# PainRegister_MCU.net
KiCad netlist of a schematic drawn in Altium Designer
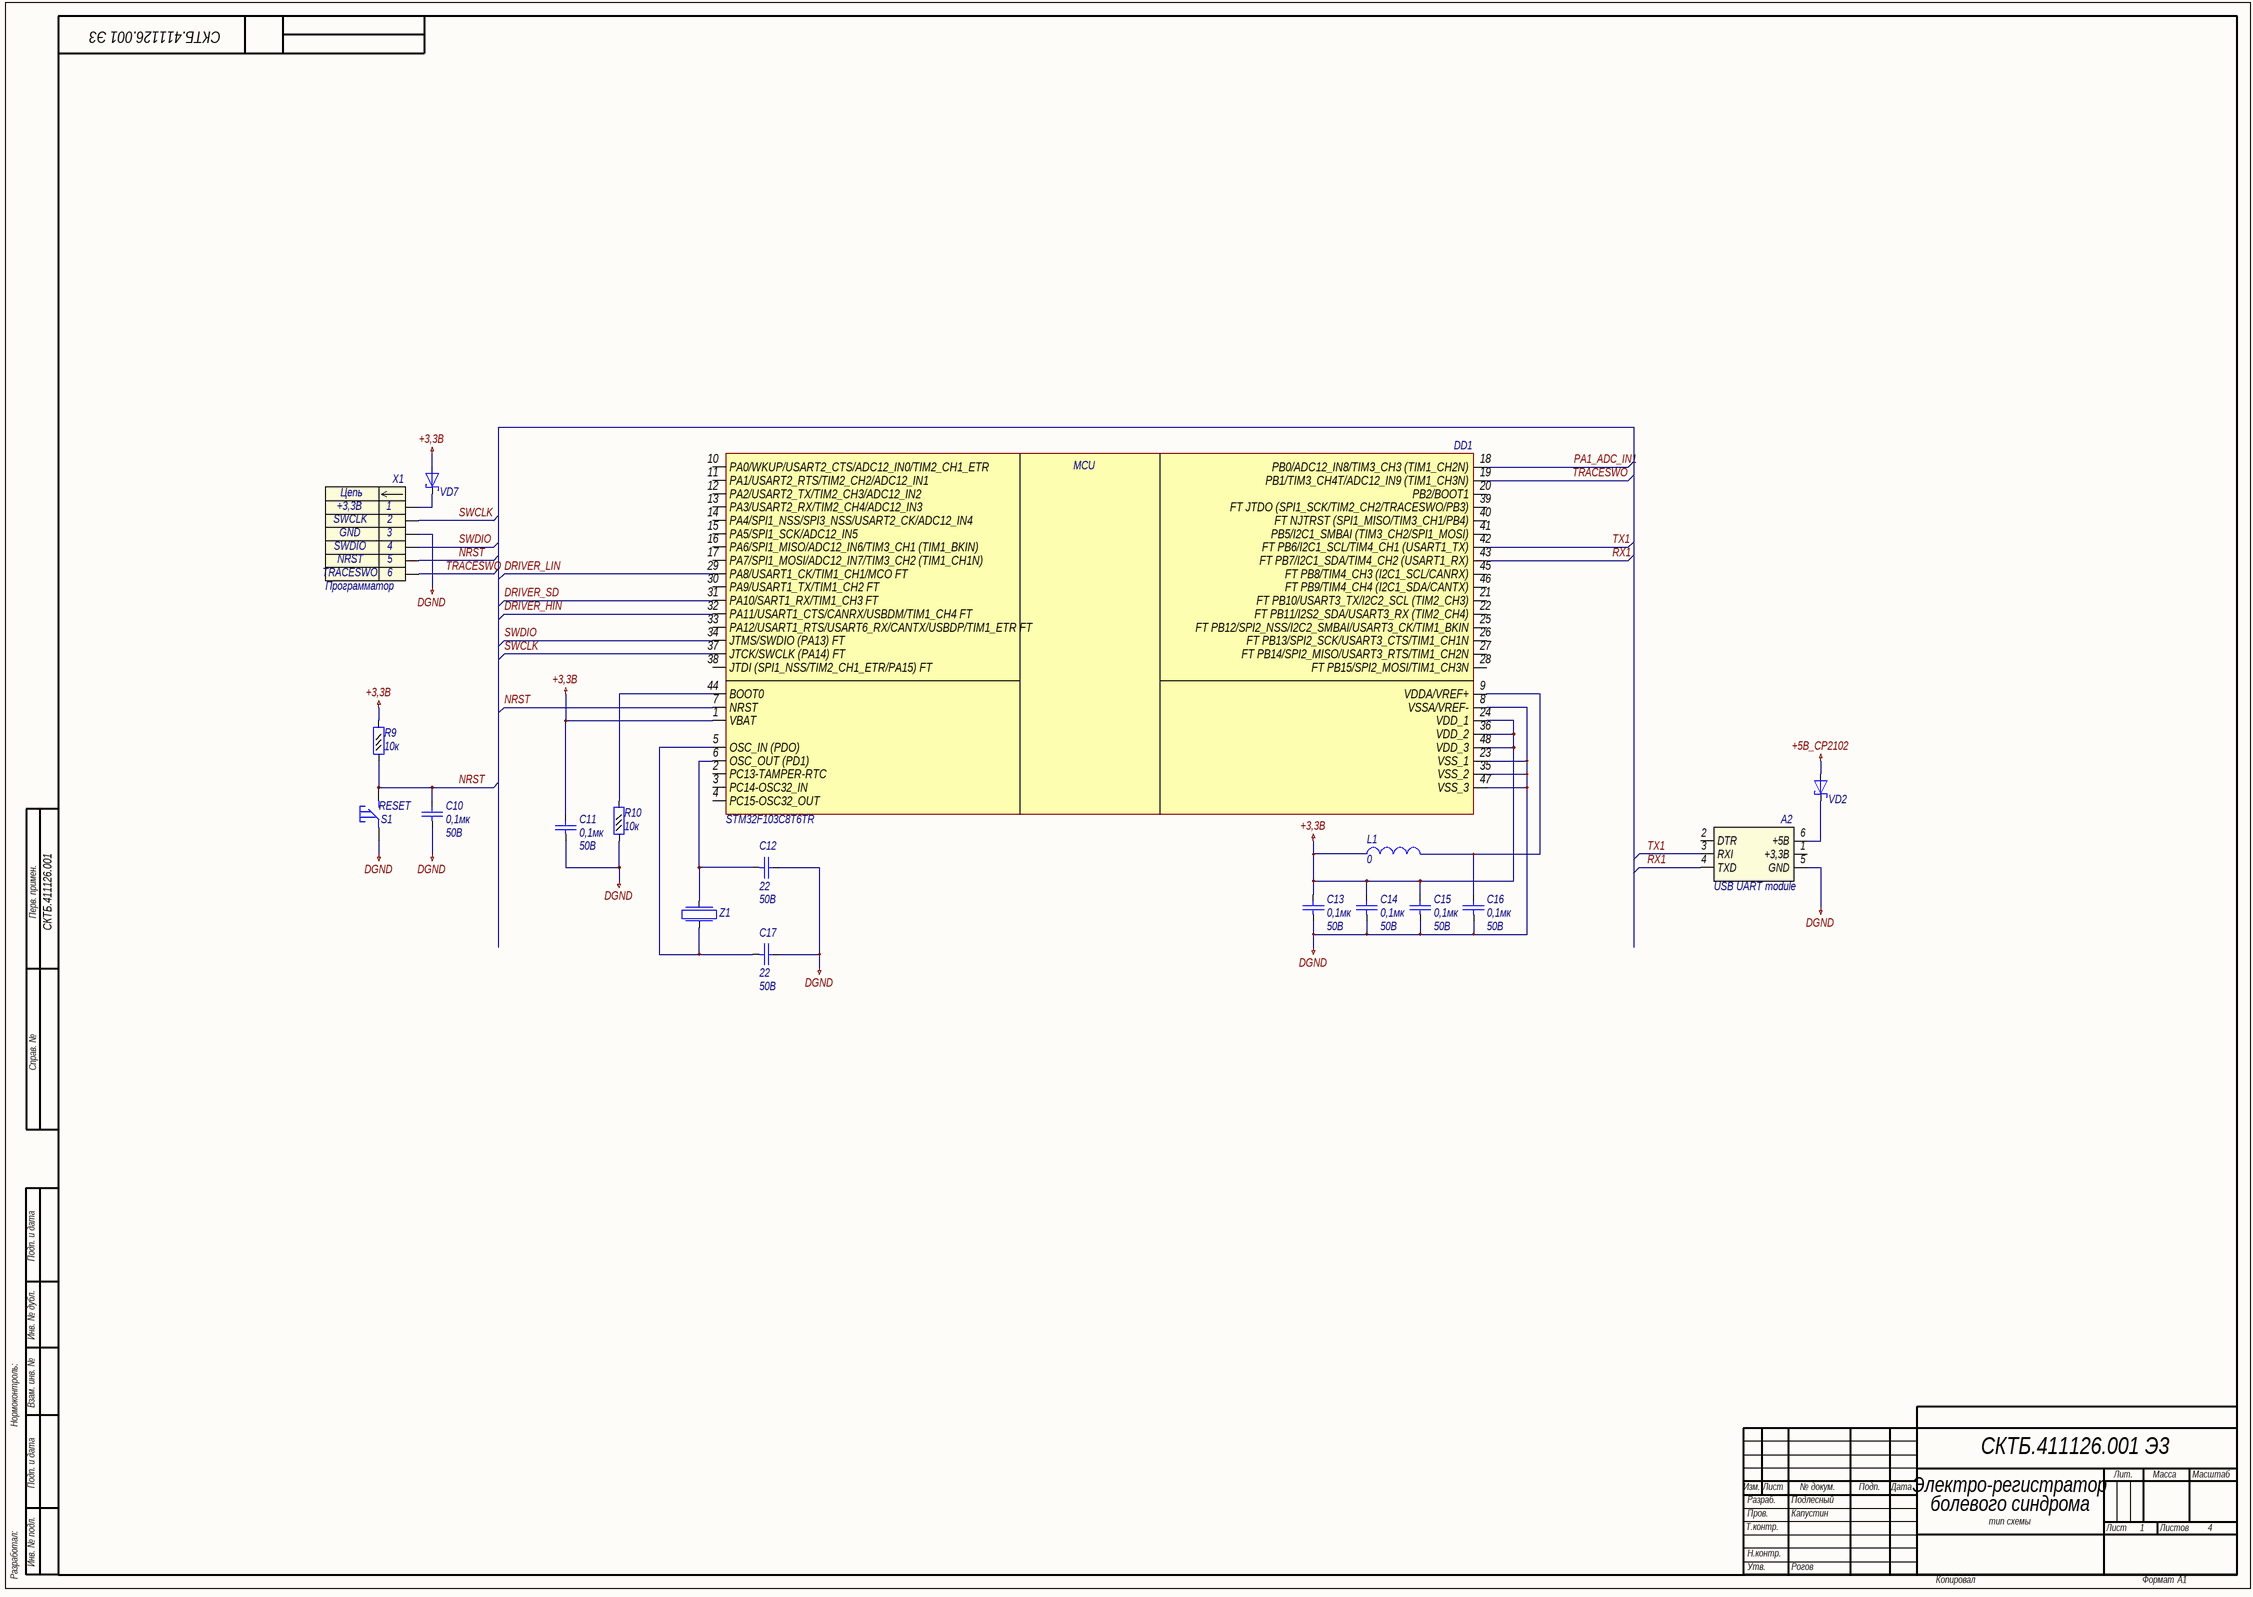
[diagram p0: PainRegister_MCU.SchDoc]

(export (version "E")
  (design (tool "Eeschema 10.0.6"))
  (components
    (comp (ref "A2")
      (value "USB UART module")
      (footprint "USB UART CP2102")
      (libsource (lib "MOP44") (part "USB UART"))
    )
    (comp (ref "C10")
      (value "0,1мк")
      (footprint "C0603")
      (description "Конденсатор")
      (fields
        (field (name "VOLTAGE") "50B")
        (field (name "PART NUMBER") "GRM188R71H104KA93D")
        (field (name "Comment") "Capacitor")
      )
      (libsource (lib "MOP44") (part "Capacitor"))
    )
    (comp (ref "C11")
      (value "0,1мк")
      (footprint "C0603")
      (description "Конденсатор")
      (fields
        (field (name "VOLTAGE") "50B")
        (field (name "PART NUMBER") "GRM188R71H104KA93D")
        (field (name "Comment") "Capacitor")
      )
      (libsource (lib "MOP44") (part "Capacitor"))
    )
    (comp (ref "C12")
      (value "22")
      (footprint "C0603")
      (description "Конденсатор")
      (fields
        (field (name "VOLTAGE") "50B")
        (field (name "PART NUMBER") "CC0603JRNPO9BN220")
        (field (name "Comment") "Capacitor")
      )
      (libsource (lib "MOP44") (part "Capacitor"))
    )
    (comp (ref "C13")
      (value "0,1мк")
      (footprint "C0603")
      (description "Конденсатор")
      (fields
        (field (name "VOLTAGE") "50B")
        (field (name "PART NUMBER") "GRM188R71H104KA93D")
        (field (name "Comment") "Capacitor")
      )
      (libsource (lib "MOP44") (part "Capacitor"))
    )
    (comp (ref "C14")
      (value "0,1мк")
      (footprint "C0603")
      (description "Конденсатор")
      (fields
        (field (name "VOLTAGE") "50B")
        (field (name "PART NUMBER") "GRM188R71H104KA93D")
        (field (name "Comment") "Capacitor")
      )
      (libsource (lib "MOP44") (part "Capacitor"))
    )
    (comp (ref "C15")
      (value "0,1мк")
      (footprint "C0603")
      (description "Конденсатор")
      (fields
        (field (name "VOLTAGE") "50B")
        (field (name "PART NUMBER") "GRM188R71H104KA93D")
        (field (name "Comment") "Capacitor")
      )
      (libsource (lib "MOP44") (part "Capacitor"))
    )
    (comp (ref "C16")
      (value "0,1мк")
      (footprint "C0603")
      (description "Конденсатор")
      (fields
        (field (name "VOLTAGE") "50B")
        (field (name "PART NUMBER") "GRM188R71H104KA93D")
        (field (name "Comment") "Capacitor")
      )
      (libsource (lib "MOP44") (part "Capacitor"))
    )
    (comp (ref "C17")
      (value "22")
      (footprint "C0603")
      (description "Конденсатор")
      (fields
        (field (name "VOLTAGE") "50B")
        (field (name "PART NUMBER") "CC0603JRNPO9BN220")
        (field (name "Comment") "Capacitor")
      )
      (libsource (lib "MOP44") (part "Capacitor"))
    )
    (comp (ref "DD1")
      (value "STM32F103C8T6TR")
      (footprint "LQFP48")
      (fields (field (name "PART NUMBER") "STM32F103C8T6TR"))
      (libsource (lib "MOP44") (part "STM32F103C8T6TR"))
    )
    (comp (ref "L1")
      (value "0")
      (footprint "L0603")
      (description "EMI Suppression Filter")
      (fields (field (name "PART NUMBER") "BLM18PG181SN1D") (field (name "Comment") "Inductor"))
      (libsource (lib "MOP44") (part "Inductor"))
    )
    (comp (ref "R9")
      (value "10к")
      (footprint "R0603")
      (description "Резистор")
      (fields (field (name "PART NUMBER") "RC0603FR-0710KL") (field (name "POWER") "0,062Вт"))
      (libsource (lib "MOP44") (part "Resistor_0,062Вт"))
    )
    (comp (ref "R10")
      (value "10к")
      (footprint "R0603")
      (description "Резистор")
      (fields (field (name "PART NUMBER") "RC0603FR-0710KL") (field (name "POWER") "0,062Вт"))
      (libsource (lib "MOP44") (part "Resistor_0,062Вт"))
    )
    (comp (ref "S1")
      (value "RESET")
      (footprint "Button_SMD")
      (description "Кнопка")
      (libsource (lib "MOP44") (part "Button"))
    )
    (comp (ref "VD2")
      (value "DiodeSchottky")
      (footprint "SOD-523")
      (description "Диод Шоттки")
      (fields (field (name "PART NUMBER") "PMEG2010AEB.115"))
      (libsource (lib "MOP44") (part "DiodeSchottky"))
    )
    (comp (ref "VD7")
      (value "DiodeSchottky")
      (footprint "SOD-523")
      (description "Диод Шоттки")
      (fields (field (name "PART NUMBER") "PMEG2010AEB.115"))
      (libsource (lib "MOP44") (part "DiodeSchottky"))
    )
    (comp (ref "X1")
      (value "Программатор")
      (footprint "PLS-6")
      (description "Разъем - 6 конт. вилка")
      (fields (field (name "PART NUMBER") "DS1021-1*6SF112-B"))
      (libsource (lib "MOP44") (part "Header_6_plg"))
    )
    (comp (ref "Z1")
      (value "Crystal")
      (footprint "QSMD5.0x3.2x1.0")
      (description "Кварцевый резонатор")
      (fields (field (name "PART NUMBER") "KX-9A"))
      (libsource (lib "MOP44") (part "Crystal"))
    )
  )
  (nets
    (net (code "1") (name "+3,3В") (class "Default")
      (node (ref "C11") (pin "2") (pinfunction "2_2") (pintype "passive"))
      (node (ref "C13") (pin "2") (pinfunction "2_2") (pintype "passive"))
      (node (ref "C14") (pin "2") (pinfunction "2_2") (pintype "passive"))
      (node (ref "C15") (pin "2") (pinfunction "2_2") (pintype "passive"))
      (node (ref "DD1") (pin "1") (pinfunction "VBAT_1") (pintype "passive"))
      (node (ref "DD1") (pin "24") (pinfunction "VDD_1_24") (pintype "passive"))
      (node (ref "DD1") (pin "36") (pinfunction "VDD_2_36") (pintype "passive"))
      (node (ref "DD1") (pin "48") (pinfunction "VDD_3_48") (pintype "passive"))
      (node (ref "L1") (pin "1") (pinfunction "1_1") (pintype "passive"))
      (node (ref "R9") (pin "2") (pinfunction "2_2") (pintype "passive"))
      (node (ref "VD7") (pin "2") (pinfunction "A_2") (pintype "passive"))
    )
    (net (code "2") (name "+5B_CP2102") (class "Default")
      (node (ref "VD2") (pin "2") (pinfunction "A_2") (pintype "passive"))
    )
    (net (code "3") (name "/DRIVER_HIN") (class "Default")
      (node (ref "DD1") (pin "32") (pinfunction "PA11/USART1_CTS/CANRX/USBDM/TIM1_CH4_FT_32") (pintype "passive"))
    )
    (net (code "4") (name "/DRIVER_LIN") (class "Default")
      (node (ref "DD1") (pin "29") (pinfunction "PA8/USART1_CK/TIM1_CH1/MCO_FT_29") (pintype "passive"))
    )
    (net (code "5") (name "/DRIVER_SD") (class "Default")
      (node (ref "DD1") (pin "31") (pinfunction "PA10/SART1_RX/TIM1_CH3_FT_31") (pintype "passive"))
    )
    (net (code "6") (name "/NRST") (class "Default")
      (node (ref "C10") (pin "2") (pinfunction "2_2") (pintype "passive"))
      (node (ref "DD1") (pin "7") (pinfunction "NRST_7") (pintype "passive"))
      (node (ref "R9") (pin "1") (pinfunction "1_1") (pintype "passive"))
      (node (ref "S1") (pin "4") (pinfunction "4_4") (pintype "passive"))
      (node (ref "X1") (pin "5") (pinfunction "5_5") (pintype "passive"))
    )
    (net (code "7") (name "/PA1_ADC_IN1") (class "Default")
      (node (ref "DD1") (pin "18") (pinfunction "PB0/ADC12_IN8/TIM3_CH3_(TIM1_CH2N)_18") (pintype "passive"))
    )
    (net (code "8") (name "/RX1") (class "Default")
      (node (ref "A2") (pin "4") (pinfunction "TXD_4") (pintype "power_in"))
      (node (ref "DD1") (pin "43") (pinfunction "FT_PB7/I2C1_SDA/TIM4_CH2_(USART1_RX)_43") (pintype "passive"))
    )
    (net (code "9") (name "/SWCLK") (class "Default")
      (node (ref "DD1") (pin "37") (pinfunction "JTCK/SWCLK_(PA14)_FT_37") (pintype "passive"))
      (node (ref "X1") (pin "2") (pinfunction "2_2") (pintype "passive"))
    )
    (net (code "10") (name "/SWDIO") (class "Default")
      (node (ref "DD1") (pin "34") (pinfunction "JTMS/SWDIO_(PA13)_FT_34") (pintype "passive"))
      (node (ref "X1") (pin "4") (pinfunction "4_4") (pintype "passive"))
    )
    (net (code "11") (name "/TRACESWO") (class "Default")
      (node (ref "DD1") (pin "19") (pinfunction "PB1/TIM3_CH4T/ADC12_IN9_(TIM1_CH3N)_19") (pintype "passive"))
      (node (ref "X1") (pin "6") (pinfunction "6_6") (pintype "passive"))
    )
    (net (code "12") (name "/TX1") (class "Default")
      (node (ref "A2") (pin "3") (pinfunction "RXI_3") (pintype "power_in"))
      (node (ref "DD1") (pin "42") (pinfunction "FT_PB6/I2C1_SCL/TIM4_CH1_(USART1_TX)_42") (pintype "passive"))
    )
    (net (code "13") (name "DGND") (class "Default")
      (node (ref "A2") (pin "5") (pinfunction "GND_5") (pintype "power_in"))
      (node (ref "C10") (pin "1") (pinfunction "1_1") (pintype "passive"))
      (node (ref "C11") (pin "1") (pinfunction "1_1") (pintype "passive"))
      (node (ref "C12") (pin "2") (pinfunction "2_2") (pintype "passive"))
      (node (ref "C13") (pin "1") (pinfunction "1_1") (pintype "passive"))
      (node (ref "C14") (pin "1") (pinfunction "1_1") (pintype "passive"))
      (node (ref "C15") (pin "1") (pinfunction "1_1") (pintype "passive"))
      (node (ref "C16") (pin "1") (pinfunction "1_1") (pintype "passive"))
      (node (ref "C17") (pin "2") (pinfunction "2_2") (pintype "passive"))
      (node (ref "DD1") (pin "23") (pinfunction "VSS_1_23") (pintype "passive"))
      (node (ref "DD1") (pin "35") (pinfunction "VSS_2_35") (pintype "passive"))
      (node (ref "DD1") (pin "47") (pinfunction "VSS_3_47") (pintype "passive"))
      (node (ref "DD1") (pin "8") (pinfunction "VSSA/VREF-_8") (pintype "passive"))
      (node (ref "R10") (pin "1") (pinfunction "1_1") (pintype "passive"))
      (node (ref "S1") (pin "1") (pinfunction "1_1") (pintype "passive"))
      (node (ref "X1") (pin "3") (pinfunction "3_3") (pintype "passive"))
    )
    (net (code "14") (name "Net-(A2-+5B)") (class "Default")
      (node (ref "A2") (pin "6") (pinfunction "+5B_6") (pintype "power_in"))
      (node (ref "VD2") (pin "1") (pinfunction "K_1") (pintype "passive"))
    )
    (net (code "15") (name "Net-(DD1-BOOT0)") (class "Default")
      (node (ref "DD1") (pin "44") (pinfunction "BOOT0_44") (pintype "passive"))
      (node (ref "R10") (pin "2") (pinfunction "2_2") (pintype "passive"))
    )
    (net (code "16") (name "Net-(DD1-OSC_IN_(PDO))") (class "Default")
      (node (ref "C17") (pin "1") (pinfunction "1_1") (pintype "passive"))
      (node (ref "DD1") (pin "5") (pinfunction "OSC_IN_(PDO)_5") (pintype "passive"))
      (node (ref "Z1") (pin "1") (pinfunction "1_1") (pintype "passive"))
    )
    (net (code "17") (name "Net-(DD1-OSC_OUT_(PD1))") (class "Default")
      (node (ref "C12") (pin "1") (pinfunction "1_1") (pintype "passive"))
      (node (ref "DD1") (pin "6") (pinfunction "OSC_OUT_(PD1)_6") (pintype "passive"))
      (node (ref "Z1") (pin "2") (pinfunction "2_2") (pintype "passive"))
    )
    (net (code "18") (name "Net-(DD1-VDDA{slash}VREF+)") (class "Default")
      (node (ref "C16") (pin "2") (pinfunction "2_2") (pintype "passive"))
      (node (ref "DD1") (pin "9") (pinfunction "VDDA/VREF+_9") (pintype "passive"))
      (node (ref "L1") (pin "2") (pinfunction "2_2") (pintype "passive"))
    )
    (net (code "19") (name "Net-(VD7-K)") (class "Default")
      (node (ref "VD7") (pin "1") (pinfunction "K_1") (pintype "passive"))
      (node (ref "X1") (pin "1") (pinfunction "1_1") (pintype "passive"))
    )
    (net (code "20") (name "unconnected-(A2-+3,3B-Pad1)") (class "Default")
      (node (ref "A2") (pin "1") (pinfunction "+3,3B_1") (pintype "power_in"))
    )
    (net (code "21") (name "unconnected-(A2-DTR-Pad2)") (class "Default")
      (node (ref "A2") (pin "2") (pinfunction "DTR_2") (pintype "power_in"))
    )
    (net (code "22") (name "unconnected-(DD1-FT_JTDO_(SPI1_SCK{slash}TIM2_CH2{slash}TRACESWO{slash}PB3)-Pad39)") (class "Default")
      (node (ref "DD1") (pin "39") (pinfunction "FT_JTDO_(SPI1_SCK/TIM2_CH2/TRACESWO/PB3)_39") (pintype "passive"))
    )
    (net (code "23") (name "unconnected-(DD1-FT_NJTRST_(SPI1_MISO{slash}TIM3_CH1{slash}PB4)-Pad40)") (class "Default")
      (node (ref "DD1") (pin "40") (pinfunction "FT_NJTRST_(SPI1_MISO/TIM3_CH1/PB4)_40") (pintype "passive"))
    )
    (net (code "24") (name "unconnected-(DD1-FT_PB8{slash}TIM4_CH3_(I2C1_SCL{slash}CANRX)-Pad45)") (class "Default")
      (node (ref "DD1") (pin "45") (pinfunction "FT_PB8/TIM4_CH3_(I2C1_SCL/CANRX)_45") (pintype "passive"))
    )
    (net (code "25") (name "unconnected-(DD1-FT_PB9{slash}TIM4_CH4_(I2C1_SDA{slash}CANTX)-Pad46)") (class "Default")
      (node (ref "DD1") (pin "46") (pinfunction "FT_PB9/TIM4_CH4_(I2C1_SDA/CANTX)_46") (pintype "passive"))
    )
    (net (code "26") (name "unconnected-(DD1-FT_PB10{slash}USART3_TX{slash}I2C2_SCL_(TIM2_CH3)-Pad21)") (class "Default")
      (node (ref "DD1") (pin "21") (pinfunction "FT_PB10/USART3_TX/I2C2_SCL_(TIM2_CH3)_21") (pintype "passive"))
    )
    (net (code "27") (name "unconnected-(DD1-FT_PB11{slash}I2S2_SDA{slash}USART3_RX_(TIM2_CH4)-Pad22)") (class "Default")
      (node (ref "DD1") (pin "22") (pinfunction "FT_PB11/I2S2_SDA/USART3_RX_(TIM2_CH4)_22") (pintype "passive"))
    )
    (net (code "28") (name "unconnected-(DD1-FT_PB12{slash}SPI2_NSS{slash}I2C2_SMBAI{slash}USART3_CK{slash}TIM1_BKIN-Pad25)") (class "Default")
      (node (ref "DD1") (pin "25") (pinfunction "FT_PB12/SPI2_NSS/I2C2_SMBAI/USART3_CK/TIM1_BKIN_25") (pintype "passive"))
    )
    (net (code "29") (name "unconnected-(DD1-FT_PB13{slash}SPI2_SCK{slash}USART3_CTS{slash}TIM1_CH1N-Pad26)") (class "Default")
      (node (ref "DD1") (pin "26") (pinfunction "FT_PB13/SPI2_SCK/USART3_CTS/TIM1_CH1N_26") (pintype "passive"))
    )
    (net (code "30") (name "unconnected-(DD1-FT_PB14{slash}SPI2_MISO{slash}USART3_RTS{slash}TIM1_CH2N-Pad27)") (class "Default")
      (node (ref "DD1") (pin "27") (pinfunction "FT_PB14/SPI2_MISO/USART3_RTS/TIM1_CH2N_27") (pintype "passive"))
    )
    (net (code "31") (name "unconnected-(DD1-FT_PB15{slash}SPI2_MOSI{slash}TIM1_CH3N-Pad28)") (class "Default")
      (node (ref "DD1") (pin "28") (pinfunction "FT_PB15/SPI2_MOSI/TIM1_CH3N_28") (pintype "passive"))
    )
    (net (code "32") (name "unconnected-(DD1-JTDI_(SPI1_NSS{slash}TIM2_CH1_ETR{slash}PA15)_FT-Pad38)") (class "Default")
      (node (ref "DD1") (pin "38") (pinfunction "JTDI_(SPI1_NSS/TIM2_CH1_ETR/PA15)_FT_38") (pintype "passive"))
    )
    (net (code "33") (name "unconnected-(DD1-PA0{slash}WKUP{slash}USART2_CTS{slash}ADC12_IN0{slash}TIM2_CH1_ETR-Pad10)") (class "Default")
      (node (ref "DD1") (pin "10") (pinfunction "PA0/WKUP/USART2_CTS/ADC12_IN0/TIM2_CH1_ETR_10") (pintype "passive"))
    )
    (net (code "34") (name "unconnected-(DD1-PA1{slash}USART2_RTS{slash}TIM2_CH2{slash}ADC12_IN1-Pad11)") (class "Default")
      (node (ref "DD1") (pin "11") (pinfunction "PA1/USART2_RTS/TIM2_CH2/ADC12_IN1_11") (pintype "passive"))
    )
    (net (code "35") (name "unconnected-(DD1-PA2{slash}USART2_TX{slash}TIM2_CH3{slash}ADC12_IN2-Pad12)") (class "Default")
      (node (ref "DD1") (pin "12") (pinfunction "PA2/USART2_TX/TIM2_CH3/ADC12_IN2_12") (pintype "passive"))
    )
    (net (code "36") (name "unconnected-(DD1-PA3{slash}USART2_RX{slash}TIM2_CH4{slash}ADC12_IN3-Pad13)") (class "Default")
      (node (ref "DD1") (pin "13") (pinfunction "PA3/USART2_RX/TIM2_CH4/ADC12_IN3_13") (pintype "passive"))
    )
    (net (code "37") (name "unconnected-(DD1-PA4{slash}SPI1_NSS{slash}SPI3_NSS{slash}USART2_CK{slash}ADC12_IN4-Pad14)") (class "Default")
      (node (ref "DD1") (pin "14") (pinfunction "PA4/SPI1_NSS/SPI3_NSS/USART2_CK/ADC12_IN4_14") (pintype "passive"))
    )
    (net (code "38") (name "unconnected-(DD1-PA5{slash}SPI1_SCK{slash}ADC12_IN5-Pad15)") (class "Default")
      (node (ref "DD1") (pin "15") (pinfunction "PA5/SPI1_SCK/ADC12_IN5_15") (pintype "passive"))
    )
    (net (code "39") (name "unconnected-(DD1-PA6{slash}SPI1_MISO{slash}ADC12_IN6{slash}TIM3_CH1_(TIM1_BKIN)-Pad16)") (class "Default")
      (node (ref "DD1") (pin "16") (pinfunction "PA6/SPI1_MISO/ADC12_IN6/TIM3_CH1_(TIM1_BKIN)_16") (pintype "passive"))
    )
    (net (code "40") (name "unconnected-(DD1-PA7{slash}SPI1_MOSI{slash}ADC12_IN7{slash}TIM3_CH2_(TIM1_CH1N)-Pad17)") (class "Default")
      (node (ref "DD1") (pin "17") (pinfunction "PA7/SPI1_MOSI/ADC12_IN7/TIM3_CH2_(TIM1_CH1N)_17") (pintype "passive"))
    )
    (net (code "41") (name "unconnected-(DD1-PA9{slash}USART1_TX{slash}TIM1_CH2_FT-Pad30)") (class "Default")
      (node (ref "DD1") (pin "30") (pinfunction "PA9/USART1_TX/TIM1_CH2_FT_30") (pintype "passive"))
    )
    (net (code "42") (name "unconnected-(DD1-PA12{slash}USART1_RTS{slash}USART6_RX{slash}CANTX{slash}USBDP{slash}TIM1_ETR_FT-Pad33)") (class "Default")
      (node (ref "DD1") (pin "33") (pinfunction "PA12/USART1_RTS/USART6_RX/CANTX/USBDP/TIM1_ETR_FT_33") (pintype "passive"))
    )
    (net (code "43") (name "unconnected-(DD1-PB2{slash}BOOT1-Pad20)") (class "Default")
      (node (ref "DD1") (pin "20") (pinfunction "PB2/BOOT1_20") (pintype "passive"))
    )
    (net (code "44") (name "unconnected-(DD1-PB5{slash}I2C1_SMBAI_(TIM3_CH2{slash}SPI1_MOSI)-Pad41)") (class "Default")
      (node (ref "DD1") (pin "41") (pinfunction "PB5/I2C1_SMBAI_(TIM3_CH2/SPI1_MOSI)_41") (pintype "passive"))
    )
    (net (code "45") (name "unconnected-(DD1-PC13-TAMPER-RTC-Pad2)") (class "Default")
      (node (ref "DD1") (pin "2") (pinfunction "PC13-TAMPER-RTC_2") (pintype "passive"))
    )
    (net (code "46") (name "unconnected-(DD1-PC14-OSC32_IN-Pad3)") (class "Default")
      (node (ref "DD1") (pin "3") (pinfunction "PC14-OSC32_IN_3") (pintype "passive"))
    )
    (net (code "47") (name "unconnected-(DD1-PC15-OSC32_OUT-Pad4)") (class "Default")
      (node (ref "DD1") (pin "4") (pinfunction "PC15-OSC32_OUT_4") (pintype "passive"))
    )
  )
)
